# button_breakout.net
KiCad netlist of a schematic drawn in EAGLE
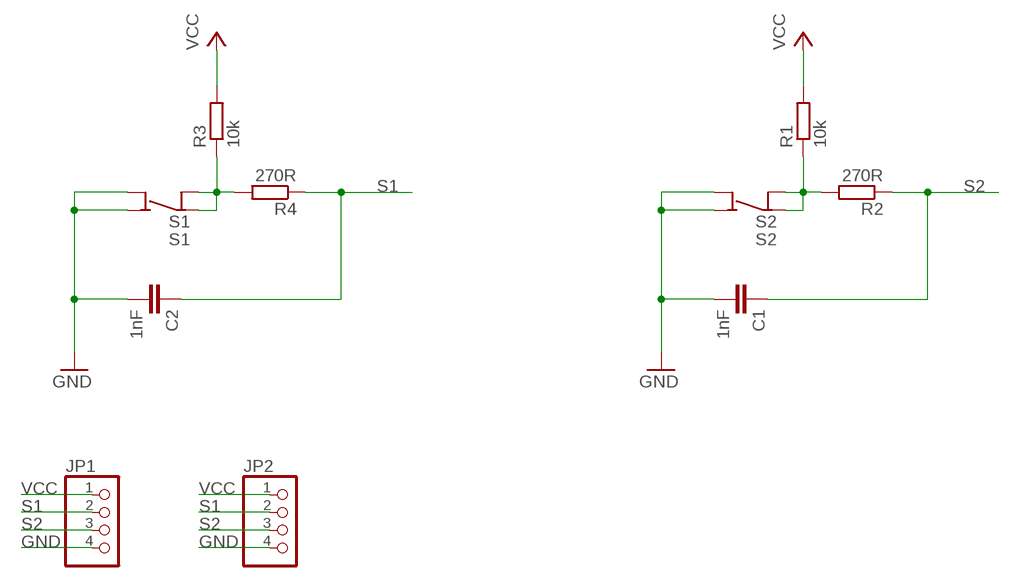
[diagram p0: schematic, sheet 1]

(export (version "E")
  (design (tool "Eeschema 10.0.6"))
  (components
    (comp (ref "C1")
      (value "1nF")
      (footprint "eagle-import:C0805")
      (libsource (lib "eagle-import") (part "C-EUC0805"))
    )
    (comp (ref "C2")
      (value "1nF")
      (footprint "eagle-import:C0805")
      (libsource (lib "eagle-import") (part "C-EUC0805"))
    )
    (comp (ref "JP1")
      (value "PINHD-1X4")
      (footprint "eagle-import:1X04")
      (libsource (lib "eagle-import") (part "PINHD-1X4"))
    )
    (comp (ref "JP2")
      (value "PINHD-1X4")
      (footprint "eagle-import:1X04")
      (libsource (lib "eagle-import") (part "PINHD-1X4"))
    )
    (comp (ref "R1")
      (value "10k")
      (footprint "eagle-import:R0805")
      (libsource (lib "eagle-import") (part "R-EU_R0805"))
    )
    (comp (ref "R2")
      (value "270R")
      (footprint "eagle-import:R0805")
      (libsource (lib "eagle-import") (part "R-EU_R0805"))
    )
    (comp (ref "R3")
      (value "10k")
      (footprint "eagle-import:R0805")
      (libsource (lib "eagle-import") (part "R-EU_R0805"))
    )
    (comp (ref "R4")
      (value "270R")
      (footprint "eagle-import:R0805")
      (libsource (lib "eagle-import") (part "R-EU_R0805"))
    )
    (comp (ref "S1")
      (value "S1")
      (footprint "eagle-import:6MMTACTILE_4PIN")
      (libsource (lib "eagle-import") (part "SPST4"))
    )
    (comp (ref "S2")
      (value "S2")
      (footprint "eagle-import:6MMTACTILE_4PIN")
      (libsource (lib "eagle-import") (part "SPST4"))
    )
  )
  (nets
    (net (code "1") (name "/S1") (class "Default")
      (node (ref "C2") (pin "1") (pinfunction "1_1") (pintype "passive"))
      (node (ref "JP1") (pin "2") (pinfunction "2_2") (pintype "passive"))
      (node (ref "JP2") (pin "2") (pinfunction "2_2") (pintype "passive"))
      (node (ref "R4") (pin "1") (pinfunction "1_1") (pintype "passive"))
    )
    (net (code "2") (name "/S2") (class "Default")
      (node (ref "C1") (pin "1") (pinfunction "1_1") (pintype "passive"))
      (node (ref "JP1") (pin "3") (pinfunction "3_3") (pintype "passive"))
      (node (ref "JP2") (pin "3") (pinfunction "3_3") (pintype "passive"))
      (node (ref "R2") (pin "1") (pinfunction "1_1") (pintype "passive"))
    )
    (net (code "3") (name "GND") (class "Default")
      (node (ref "C1") (pin "2") (pinfunction "2_2") (pintype "passive"))
      (node (ref "C2") (pin "2") (pinfunction "2_2") (pintype "passive"))
      (node (ref "JP1") (pin "4") (pinfunction "4_4") (pintype "passive"))
      (node (ref "JP2") (pin "4") (pinfunction "4_4") (pintype "passive"))
      (node (ref "S1") (pin "A1") (pinfunction "NO_A1") (pintype "passive"))
      (node (ref "S1") (pin "A2") (pinfunction "NO_A2") (pintype "passive"))
      (node (ref "S2") (pin "A1") (pinfunction "NO_A1") (pintype "passive"))
      (node (ref "S2") (pin "A2") (pinfunction "NO_A2") (pintype "passive"))
    )
    (net (code "4") (name "Net-(R1-Pad1)") (class "Default")
      (node (ref "R1") (pin "1") (pinfunction "1_1") (pintype "passive"))
      (node (ref "R2") (pin "2") (pinfunction "2_2") (pintype "passive"))
      (node (ref "S2") (pin "B1") (pinfunction "COM_B1") (pintype "passive"))
      (node (ref "S2") (pin "B2") (pinfunction "COM_B2") (pintype "passive"))
    )
    (net (code "5") (name "Net-(R3-Pad1)") (class "Default")
      (node (ref "R3") (pin "1") (pinfunction "1_1") (pintype "passive"))
      (node (ref "R4") (pin "2") (pinfunction "2_2") (pintype "passive"))
      (node (ref "S1") (pin "B1") (pinfunction "COM_B1") (pintype "passive"))
      (node (ref "S1") (pin "B2") (pinfunction "COM_B2") (pintype "passive"))
    )
    (net (code "6") (name "VCC") (class "Default")
      (node (ref "JP1") (pin "1") (pinfunction "1_1") (pintype "passive"))
      (node (ref "JP2") (pin "1") (pinfunction "1_1") (pintype "passive"))
      (node (ref "R1") (pin "2") (pinfunction "2_2") (pintype "passive"))
      (node (ref "R3") (pin "2") (pinfunction "2_2") (pintype "passive"))
    )
  )
)
